# example.net
KiCad netlist of a schematic drawn in EAGLE
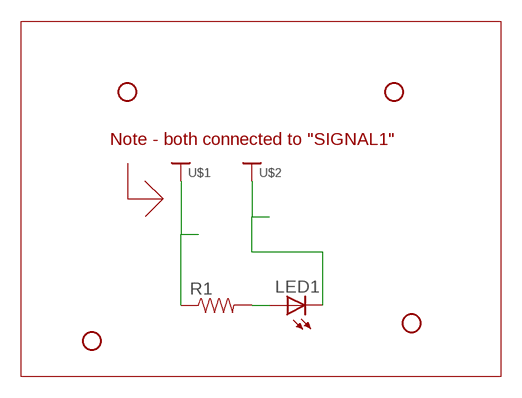
[diagram p0: schematic, sheet 1]

(export (version "E")
  (design (tool "Eeschema 10.0.6"))
  (components
    (comp (ref "JP1")
      (value "STAND-OFF")
      (footprint "eagle-import:STAND-OFF")
      (libsource (lib "eagle-import") (part "STAND-OFF"))
    )
    (comp (ref "JP2")
      (value "STAND-OFF")
      (footprint "eagle-import:STAND-OFF")
      (libsource (lib "eagle-import") (part "STAND-OFF"))
    )
    (comp (ref "JP3")
      (value "STAND-OFF")
      (footprint "eagle-import:STAND-OFF")
      (libsource (lib "eagle-import") (part "STAND-OFF"))
    )
    (comp (ref "JP4")
      (value "STAND-OFF")
      (footprint "eagle-import:STAND-OFF")
      (libsource (lib "eagle-import") (part "STAND-OFF"))
    )
    (comp (ref "LED1")
      (value "LED-FKIT-1206")
      (footprint "eagle-import:FKIT-LED-1206")
      (libsource (lib "eagle-import") (part "LED-FKIT-1206"))
    )
    (comp (ref "R1")
      (value "RESISTOR0805-RES")
      (footprint "eagle-import:0805")
      (libsource (lib "eagle-import") (part "RESISTOR0805-RES"))
    )
    (comp (ref "U$1")
      (value "HIGHCURRENTPAD2")
      (footprint "eagle-import:HIGH_CURRENT_PAD2")
      (libsource (lib "eagle-import") (part "HIGHCURRENTPAD2"))
    )
    (comp (ref "U$2")
      (value "HIGHCURRENTPAD2")
      (footprint "eagle-import:HIGH_CURRENT_PAD2")
      (libsource (lib "eagle-import") (part "HIGHCURRENTPAD2"))
    )
  )
  (nets
    (net (code "1") (name "/SIGNAL1") (class "Default")
      (node (ref "LED1") (pin "C") (pinfunction "C_C") (pintype "passive"))
      (node (ref "R1") (pin "1") (pinfunction "1_1") (pintype "passive"))
      (node (ref "U$1") (pin "P$1") (pinfunction "P$1_P$1") (pintype "bidirectional"))
      (node (ref "U$2") (pin "P$1") (pinfunction "P$1_P$1") (pintype "bidirectional"))
    )
    (net (code "2") (name "Net-(LED1-PadA)") (class "Default")
      (node (ref "LED1") (pin "A") (pinfunction "A_A") (pintype "passive"))
      (node (ref "R1") (pin "2") (pinfunction "2_2") (pintype "passive"))
    )
  )
)
